# 2_x_Stepper_Motoren_Midi_Board_01.net
KiCad netlist of a schematic drawn in EAGLE
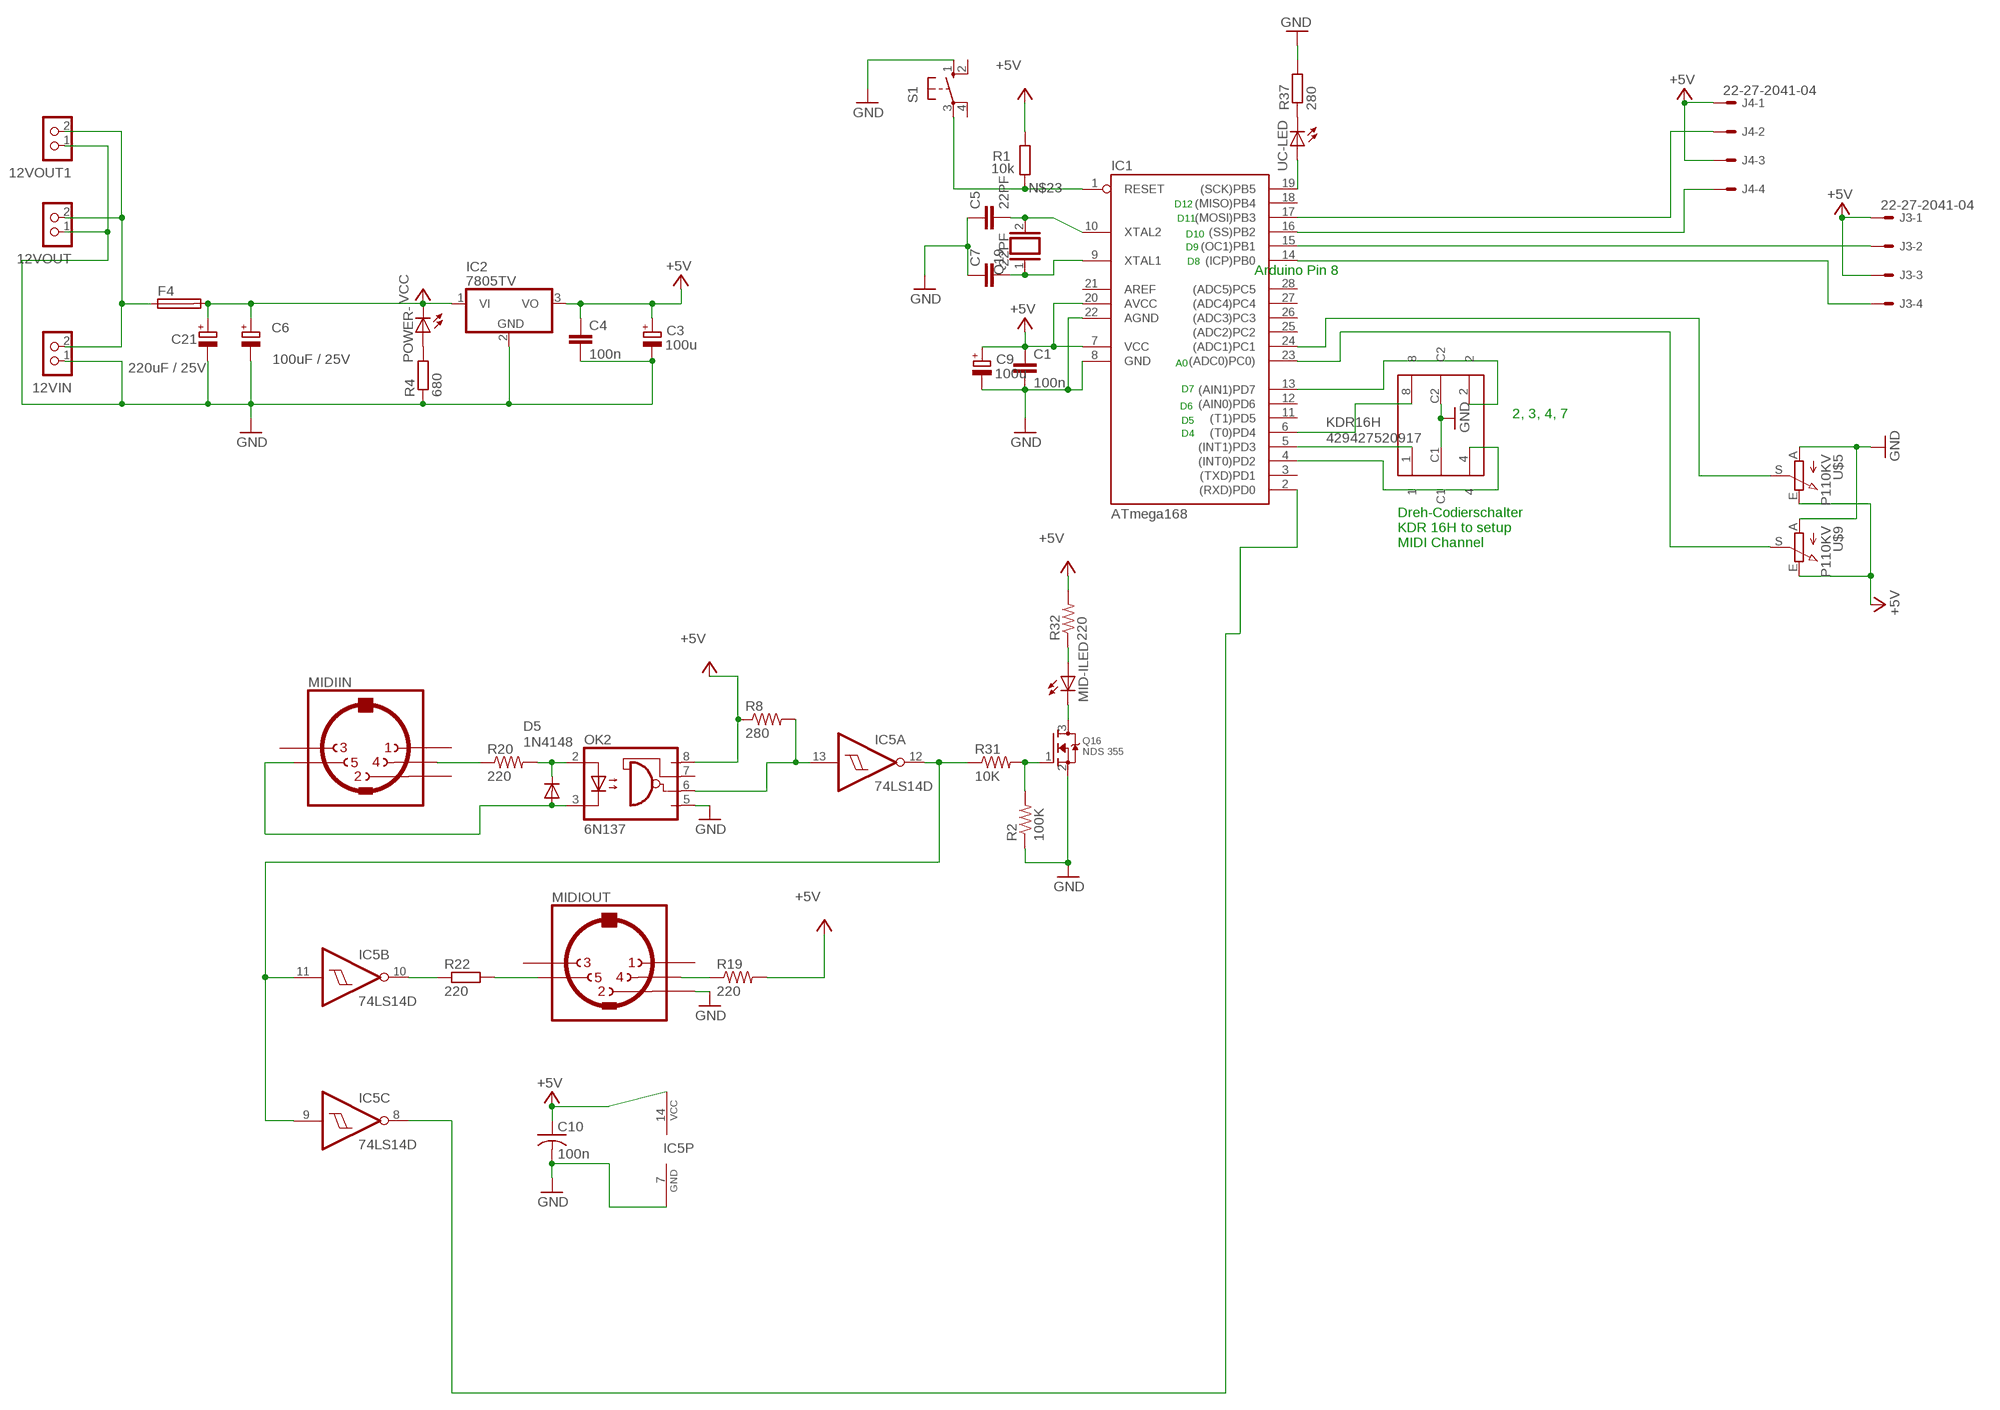
[diagram p0: schematic, sheet 1]

(export (version "E")
  (design (tool "Eeschema 10.0.6"))
  (components
    (comp (ref "12VIN")
      (value "CON_TERMINAL_BLOCK_02-5MM")
      (footprint "eagle-import:TERMINAL_BLOCK_2P_5")
      (libsource (lib "eagle-import") (part "CON_TERMINAL_BLOCK_02-5MM"))
    )
    (comp (ref "12VOUT")
      (value "CON_TERMINAL_BLOCK_02-5MM")
      (footprint "eagle-import:TERMINAL_BLOCK_2P_5")
      (libsource (lib "eagle-import") (part "CON_TERMINAL_BLOCK_02-5MM"))
    )
    (comp (ref "12VOUT1")
      (value "CON_TERMINAL_BLOCK_02-5MM")
      (footprint "eagle-import:TERMINAL_BLOCK_2P_5")
      (libsource (lib "eagle-import") (part "CON_TERMINAL_BLOCK_02-5MM"))
    )
    (comp (ref "C1")
      (value "100n")
      (footprint "eagle-import:C0805K")
      (libsource (lib "eagle-import") (part "C-EUC0805K"))
    )
    (comp (ref "C3")
      (value "100u")
      (footprint "eagle-import:E2,5-7")
      (libsource (lib "eagle-import") (part "CPOL-EUE2.5-7"))
    )
    (comp (ref "C4")
      (value "100n")
      (footprint "eagle-import:C0805K")
      (libsource (lib "eagle-import") (part "C-EUC0805K"))
    )
    (comp (ref "C5")
      (value "22PF")
      (footprint "eagle-import:C0805")
      (libsource (lib "eagle-import") (part "rcl_C-EUC0805"))
    )
    (comp (ref "C6")
      (value "100uF / 25V")
      (footprint "eagle-import:E2,5-7")
      (libsource (lib "eagle-import") (part "CPOL-EUE2.5-7"))
    )
    (comp (ref "C7")
      (value "22PF")
      (footprint "eagle-import:C0805")
      (libsource (lib "eagle-import") (part "rcl_C-EUC0805"))
    )
    (comp (ref "C9")
      (value "100u")
      (footprint "eagle-import:E2,5-6")
      (libsource (lib "eagle-import") (part "CPOL-EUE2.5-6"))
    )
    (comp (ref "C10")
      (value "100n")
      (footprint "eagle-import:C0805")
      (libsource (lib "eagle-import") (part "C-USC0805"))
    )
    (comp (ref "C21")
      (value "220uF / 25V")
      (footprint "eagle-import:E5-8,5")
      (libsource (lib "eagle-import") (part "rcl_CPOL-EUE5-8.5"))
    )
    (comp (ref "D5")
      (value "1N4148")
      (footprint "eagle-import:D-7.5")
      (libsource (lib "eagle-import") (part "DIODE-D-7.5"))
    )
    (comp (ref "F4")
      (value "SH22,5")
      (footprint "eagle-import:SH22,5")
      (fields (field (name "MF") "SCHURTER") (field (name "MPN") "0031.8201"))
      (libsource (lib "eagle-import") (part "SH22,5"))
    )
    (comp (ref "IC1")
      (value "ATmega168")
      (footprint "eagle-import:DIL28-3")
      (libsource (lib "eagle-import") (part "AT90S4433P"))
    )
    (comp (ref "IC2")
      (value "7805TV")
      (footprint "eagle-import:TO220V")
      (libsource (lib "eagle-import") (part "78TV05"))
    )
    (comp (ref "IC5")
      (value "74LS14D")
      (footprint "eagle-import:SO14")
      (libsource (lib "eagle-import") (part "7414DLS"))
    )
    (comp (ref "J3")
      (value "22-27-2041-04")
      (footprint "eagle-import:6410-04")
      (libsource (lib "eagle-import") (part "22-?-0427-2041"))
    )
    (comp (ref "J4")
      (value "22-27-2041-04")
      (footprint "eagle-import:6410-04")
      (libsource (lib "eagle-import") (part "22-?-0427-2041"))
    )
    (comp (ref "KDR16H")
      (value "429427520917")
      (footprint "eagle-import:429427520917")
      (libsource (lib "eagle-import") (part "429427520917"))
    )
    (comp (ref "MID-ILED")
      (value "LED3MM")
      (footprint "eagle-import:LED3MM")
      (libsource (lib "eagle-import") (part "LED3MM"))
    )
    (comp (ref "MIDIIN")
      (value "MAB5SH")
      (footprint "eagle-import:MAB5SH")
      (libsource (lib "eagle-import") (part "MAB5SH"))
    )
    (comp (ref "MIDIOUT")
      (value "MAB5SH")
      (footprint "eagle-import:MAB5SH")
      (libsource (lib "eagle-import") (part "MAB5SH"))
    )
    (comp (ref "OK2")
      (value "6N137")
      (footprint "eagle-import:DIL08")
      (fields
        (field (name "MPN") "6N137")
        (field (name "OC_FARNELL") "1328376")
        (field (name "OC_NEWARK") "52M1895")
      )
      (libsource (lib "eagle-import") (part "6N137"))
    )
    (comp (ref "POWER-")
      (value "LED3MM")
      (footprint "eagle-import:LED3MM")
      (libsource (lib "eagle-import") (part "LED3MM"))
    )
    (comp (ref "Q16")
      (value "NDS 355")
      (footprint "eagle-import:SOT23-W")
      (libsource (lib "eagle-import") (part "MOSFET-NWAVE"))
    )
    (comp (ref "Q19")
      (value "XTAL/S")
      (footprint "eagle-import:QS")
      (libsource (lib "eagle-import") (part "XTAL/S"))
    )
    (comp (ref "R1")
      (value "10k")
      (footprint "eagle-import:R0805")
      (libsource (lib "eagle-import") (part "R-EU_R0805"))
    )
    (comp (ref "R2")
      (value "100K")
      (footprint "eagle-import:R0805W")
      (libsource (lib "eagle-import") (part "R-US_R0805W"))
    )
    (comp (ref "R4")
      (value "680")
      (footprint "eagle-import:R0805W")
      (libsource (lib "eagle-import") (part "R-EU_R0805W"))
    )
    (comp (ref "R8")
      (value "280")
      (footprint "eagle-import:M0805")
      (libsource (lib "eagle-import") (part "R-US_M0805"))
    )
    (comp (ref "R19")
      (value "220")
      (footprint "eagle-import:R0805W")
      (libsource (lib "eagle-import") (part "R-US_R0805W"))
    )
    (comp (ref "R20")
      (value "220")
      (footprint "eagle-import:R0805")
      (libsource (lib "eagle-import") (part "R-US_R0805"))
    )
    (comp (ref "R22")
      (value "220")
      (footprint "eagle-import:R0805")
      (libsource (lib "eagle-import") (part "R-EU_R0805"))
    )
    (comp (ref "R31")
      (value "10K")
      (footprint "eagle-import:R0805W")
      (libsource (lib "eagle-import") (part "R-US_R0805W"))
    )
    (comp (ref "R32")
      (value "220")
      (footprint "eagle-import:R0805W")
      (libsource (lib "eagle-import") (part "R-US_R0805W"))
    )
    (comp (ref "R37")
      (value "280")
      (footprint "eagle-import:R0805")
      (libsource (lib "eagle-import") (part "R-EU_R0805"))
    )
    (comp (ref "S1")
      (value "10-XX")
      (footprint "eagle-import:B3F-10XX")
      (fields (field (name "MPN") "B3F-1000"))
      (libsource (lib "eagle-import") (part "10-XX"))
    )
    (comp (ref "U$5")
      (value "P110KV")
      (footprint "eagle-import:POT-P110KV")
      (libsource (lib "eagle-import") (part "P110KV"))
    )
    (comp (ref "U$9")
      (value "P110KV")
      (footprint "eagle-import:POT-P110KV")
      (libsource (lib "eagle-import") (part "P110KV"))
    )
    (comp (ref "UC-LED")
      (value "LED3MM")
      (footprint "eagle-import:LED3MM")
      (libsource (lib "eagle-import") (part "LED3MM"))
    )
  )
  (nets
    (net (code "1") (name "+5V") (class "Default")
      (node (ref "C1") (pin "1") (pinfunction "1_1") (pintype "passive"))
      (node (ref "C10") (pin "1") (pinfunction "1_1") (pintype "passive"))
      (node (ref "C3") (pin "+") (pinfunction "+_+") (pintype "passive"))
      (node (ref "C4") (pin "1") (pinfunction "1_1") (pintype "passive"))
      (node (ref "C9") (pin "+") (pinfunction "+_+") (pintype "passive"))
      (node (ref "IC1") (pin "20") (pinfunction "AVCC_20") (pintype "power_in"))
      (node (ref "IC1") (pin "7") (pinfunction "VCC_7") (pintype "power_in"))
      (node (ref "IC2") (pin "3") (pinfunction "VO_3") (pintype "passive"))
      (node (ref "IC5") (pin "14") (pinfunction "VCC_14") (pintype "power_in"))
      (node (ref "J3") (pin "1") (pinfunction "S_1") (pintype "passive"))
      (node (ref "J3") (pin "3") (pinfunction "S_3") (pintype "passive"))
      (node (ref "J4") (pin "1") (pinfunction "S_1") (pintype "passive"))
      (node (ref "J4") (pin "3") (pinfunction "S_3") (pintype "passive"))
      (node (ref "OK2") (pin "8") (pinfunction "VCC_8") (pintype "passive"))
      (node (ref "R1") (pin "2") (pinfunction "2_2") (pintype "passive"))
      (node (ref "R19") (pin "2") (pinfunction "2_2") (pintype "passive"))
      (node (ref "R32") (pin "2") (pinfunction "2_2") (pintype "passive"))
      (node (ref "R8") (pin "1") (pinfunction "1_1") (pintype "passive"))
      (node (ref "U$5") (pin "E") (pinfunction "E_E") (pintype "passive"))
      (node (ref "U$9") (pin "E") (pinfunction "E_E") (pintype "passive"))
    )
    (net (code "2") (name "/N$23") (class "Default")
      (node (ref "IC1") (pin "1") (pinfunction "RESET_1") (pintype "input"))
      (node (ref "R1") (pin "1") (pinfunction "1_1") (pintype "passive"))
      (node (ref "S1") (pin "3") (pinfunction "P_3") (pintype "passive"))
    )
    (net (code "3") (name "GND") (class "Default")
      (node (ref "12VIN") (pin "1") (pinfunction "1_1") (pintype "passive"))
      (node (ref "12VOUT") (pin "1") (pinfunction "1_1") (pintype "passive"))
      (node (ref "12VOUT1") (pin "1") (pinfunction "1_1") (pintype "passive"))
      (node (ref "C1") (pin "2") (pinfunction "2_2") (pintype "passive"))
      (node (ref "C10") (pin "2") (pinfunction "2_2") (pintype "passive"))
      (node (ref "C21") (pin "-") (pinfunction "-_-") (pintype "passive"))
      (node (ref "C3") (pin "-") (pinfunction "-_-") (pintype "passive"))
      (node (ref "C4") (pin "2") (pinfunction "2_2") (pintype "passive"))
      (node (ref "C5") (pin "1") (pinfunction "1_1") (pintype "passive"))
      (node (ref "C6") (pin "-") (pinfunction "-_-") (pintype "passive"))
      (node (ref "C7") (pin "1") (pinfunction "1_1") (pintype "passive"))
      (node (ref "C9") (pin "-") (pinfunction "-_-") (pintype "passive"))
      (node (ref "IC1") (pin "22") (pinfunction "AGND_22") (pintype "power_in"))
      (node (ref "IC1") (pin "8") (pinfunction "GND_8") (pintype "power_in"))
      (node (ref "IC2") (pin "2") (pinfunction "GND_2") (pintype "passive"))
      (node (ref "IC5") (pin "7") (pinfunction "GND_7") (pintype "power_in"))
      (node (ref "KDR16H") (pin "C1") (pinfunction "C1_C1") (pintype "bidirectional"))
      (node (ref "KDR16H") (pin "C2") (pinfunction "C2_C2") (pintype "bidirectional"))
      (node (ref "MIDIOUT") (pin "2") (pinfunction "2_2") (pintype "passive"))
      (node (ref "OK2") (pin "5") (pinfunction "GND_5") (pintype "passive"))
      (node (ref "Q16") (pin "2") (pinfunction "S_2") (pintype "bidirectional"))
      (node (ref "R2") (pin "1") (pinfunction "1_1") (pintype "passive"))
      (node (ref "R37") (pin "2") (pinfunction "2_2") (pintype "passive"))
      (node (ref "R4") (pin "1") (pinfunction "1_1") (pintype "passive"))
      (node (ref "S1") (pin "1") (pinfunction "S_1") (pintype "passive"))
      (node (ref "U$5") (pin "A") (pinfunction "A_A") (pintype "passive"))
      (node (ref "U$9") (pin "A") (pinfunction "A_A") (pintype "passive"))
    )
    (net (code "4") (name "Net-(12VIN-Pad2)") (class "Default")
      (node (ref "12VIN") (pin "2") (pinfunction "2_2") (pintype "passive"))
      (node (ref "12VOUT") (pin "2") (pinfunction "2_2") (pintype "passive"))
      (node (ref "12VOUT1") (pin "2") (pinfunction "2_2") (pintype "passive"))
      (node (ref "F4") (pin "1") (pinfunction "1_1") (pintype "passive"))
    )
    (net (code "5") (name "Net-(IC1-(ADC0)PC0))") (class "Default")
      (node (ref "IC1") (pin "23") (pinfunction "(ADC0)PC0)_23") (pintype "bidirectional"))
      (node (ref "U$9") (pin "S") (pinfunction "S_S") (pintype "passive"))
    )
    (net (code "6") (name "Net-(IC1-(ADC1)PC1)") (class "Default")
      (node (ref "IC1") (pin "24") (pinfunction "(ADC1)PC1_24") (pintype "bidirectional"))
      (node (ref "U$5") (pin "S") (pinfunction "S_S") (pintype "passive"))
    )
    (net (code "7") (name "Net-(IC1-(AIN1)PD7)") (class "Default")
      (node (ref "IC1") (pin "13") (pinfunction "(AIN1)PD7_13") (pintype "bidirectional"))
      (node (ref "KDR16H") (pin "2") (pinfunction "2_2") (pintype "bidirectional"))
    )
    (net (code "8") (name "Net-(IC1-(ICP)PB0)") (class "Default")
      (node (ref "IC1") (pin "14") (pinfunction "(ICP)PB0_14") (pintype "bidirectional"))
      (node (ref "J3") (pin "4") (pinfunction "S_4") (pintype "passive"))
    )
    (net (code "9") (name "Net-(IC1-(INT0)PD2)") (class "Default")
      (node (ref "IC1") (pin "4") (pinfunction "(INT0)PD2_4") (pintype "bidirectional"))
      (node (ref "KDR16H") (pin "4") (pinfunction "4_4") (pintype "bidirectional"))
    )
    (net (code "10") (name "Net-(IC1-(INT1)PD3)") (class "Default")
      (node (ref "IC1") (pin "5") (pinfunction "(INT1)PD3_5") (pintype "bidirectional"))
      (node (ref "KDR16H") (pin "1") (pinfunction "1_1") (pintype "bidirectional"))
    )
    (net (code "11") (name "Net-(IC1-(MOSI)PB3)") (class "Default")
      (node (ref "IC1") (pin "17") (pinfunction "(MOSI)PB3_17") (pintype "bidirectional"))
      (node (ref "J4") (pin "2") (pinfunction "S_2") (pintype "passive"))
    )
    (net (code "12") (name "Net-(IC1-(OC1)PB1)") (class "Default")
      (node (ref "IC1") (pin "15") (pinfunction "(OC1)PB1_15") (pintype "bidirectional"))
      (node (ref "J3") (pin "2") (pinfunction "S_2") (pintype "passive"))
    )
    (net (code "13") (name "Net-(IC1-(RXD)PD0)") (class "Default")
      (node (ref "IC1") (pin "2") (pinfunction "(RXD)PD0_2") (pintype "bidirectional"))
      (node (ref "IC5") (pin "8") (pinfunction "O_8") (pintype "output"))
    )
    (net (code "14") (name "Net-(IC1-(SCK)PB5)") (class "Default")
      (node (ref "IC1") (pin "19") (pinfunction "(SCK)PB5_19") (pintype "bidirectional"))
      (node (ref "UC-LED") (pin "A") (pinfunction "A_A") (pintype "passive"))
    )
    (net (code "15") (name "Net-(IC1-(SS)PB2)") (class "Default")
      (node (ref "IC1") (pin "16") (pinfunction "(SS)PB2_16") (pintype "bidirectional"))
      (node (ref "J4") (pin "4") (pinfunction "S_4") (pintype "passive"))
    )
    (net (code "16") (name "Net-(IC1-(T0)PD4)") (class "Default")
      (node (ref "IC1") (pin "6") (pinfunction "(T0)PD4_6") (pintype "bidirectional"))
      (node (ref "KDR16H") (pin "8") (pinfunction "8_8") (pintype "bidirectional"))
    )
    (net (code "17") (name "Net-(IC1-XTAL1)") (class "Default")
      (node (ref "C7") (pin "2") (pinfunction "2_2") (pintype "passive"))
      (node (ref "IC1") (pin "9") (pinfunction "XTAL1_9") (pintype "bidirectional"))
      (node (ref "Q19") (pin "1") (pinfunction "1_1") (pintype "passive"))
    )
    (net (code "18") (name "Net-(IC1-XTAL2)") (class "Default")
      (node (ref "C5") (pin "2") (pinfunction "2_2") (pintype "passive"))
      (node (ref "IC1") (pin "10") (pinfunction "XTAL2_10") (pintype "bidirectional"))
      (node (ref "Q19") (pin "2") (pinfunction "2_2") (pintype "passive"))
    )
    (net (code "19") (name "Net-(IC5A-I)") (class "Default")
      (node (ref "IC5") (pin "13") (pinfunction "I_13") (pintype "input"))
      (node (ref "OK2") (pin "6") (pinfunction "VO_6") (pintype "passive"))
      (node (ref "R8") (pin "2") (pinfunction "2_2") (pintype "passive"))
    )
    (net (code "20") (name "Net-(IC5A-O)") (class "Default")
      (node (ref "IC5") (pin "11") (pinfunction "I_11") (pintype "input"))
      (node (ref "IC5") (pin "12") (pinfunction "O_12") (pintype "output"))
      (node (ref "IC5") (pin "9") (pinfunction "I_9") (pintype "input"))
      (node (ref "R31") (pin "1") (pinfunction "1_1") (pintype "passive"))
    )
    (net (code "21") (name "Net-(IC5B-O)") (class "Default")
      (node (ref "IC5") (pin "10") (pinfunction "O_10") (pintype "output"))
      (node (ref "R22") (pin "1") (pinfunction "1_1") (pintype "passive"))
    )
    (net (code "22") (name "Net-(MID-ILED-C)") (class "Default")
      (node (ref "MID-ILED") (pin "K") (pinfunction "C_K") (pintype "passive"))
      (node (ref "Q16") (pin "3") (pinfunction "D_3") (pintype "bidirectional"))
    )
    (net (code "23") (name "Net-(MID-ILED-PadA)") (class "Default")
      (node (ref "MID-ILED") (pin "A") (pinfunction "A_A") (pintype "passive"))
      (node (ref "R32") (pin "1") (pinfunction "1_1") (pintype "passive"))
    )
    (net (code "24") (name "Net-(MIDIIN-Pad4)") (class "Default")
      (node (ref "MIDIIN") (pin "4") (pinfunction "4_4") (pintype "passive"))
      (node (ref "R20") (pin "1") (pinfunction "1_1") (pintype "passive"))
    )
    (net (code "25") (name "Net-(MIDIOUT-Pad4)") (class "Default")
      (node (ref "MIDIOUT") (pin "4") (pinfunction "4_4") (pintype "passive"))
      (node (ref "R19") (pin "1") (pinfunction "1_1") (pintype "passive"))
    )
    (net (code "26") (name "Net-(MIDIOUT-Pad5)") (class "Default")
      (node (ref "MIDIOUT") (pin "5") (pinfunction "5_5") (pintype "passive"))
      (node (ref "R22") (pin "2") (pinfunction "2_2") (pintype "passive"))
    )
    (net (code "27") (name "Net-(OK2-A)") (class "Default")
      (node (ref "D5") (pin "C") (pinfunction "C_C") (pintype "passive"))
      (node (ref "OK2") (pin "2") (pinfunction "A_2") (pintype "passive"))
      (node (ref "R20") (pin "2") (pinfunction "2_2") (pintype "passive"))
    )
    (net (code "28") (name "Net-(OK2-C)") (class "Default")
      (node (ref "D5") (pin "A") (pinfunction "A_A") (pintype "passive"))
      (node (ref "MIDIIN") (pin "5") (pinfunction "5_5") (pintype "passive"))
      (node (ref "OK2") (pin "3") (pinfunction "C_3") (pintype "passive"))
    )
    (net (code "29") (name "Net-(POWER--PadA)") (class "Default")
      (node (ref "POWER-") (pin "A") (pinfunction "A_A") (pintype "passive"))
      (node (ref "R4") (pin "2") (pinfunction "2_2") (pintype "passive"))
    )
    (net (code "30") (name "Net-(Q16-G)") (class "Default")
      (node (ref "Q16") (pin "1") (pinfunction "G_1") (pintype "bidirectional"))
      (node (ref "R2") (pin "2") (pinfunction "2_2") (pintype "passive"))
      (node (ref "R31") (pin "2") (pinfunction "2_2") (pintype "passive"))
    )
    (net (code "31") (name "Net-(UC-LED-C)") (class "Default")
      (node (ref "R37") (pin "1") (pinfunction "1_1") (pintype "passive"))
      (node (ref "UC-LED") (pin "K") (pinfunction "C_K") (pintype "passive"))
    )
    (net (code "32") (name "VCC") (class "Default")
      (node (ref "C21") (pin "+") (pinfunction "+_+") (pintype "passive"))
      (node (ref "C6") (pin "+") (pinfunction "+_+") (pintype "passive"))
      (node (ref "F4") (pin "2") (pinfunction "2_2") (pintype "passive"))
      (node (ref "IC2") (pin "1") (pinfunction "VI_1") (pintype "input"))
      (node (ref "POWER-") (pin "K") (pinfunction "C_K") (pintype "passive"))
    )
    (net (code "33") (name "unconnected-(IC1-(ADC2)PC2-Pad25)") (class "Default")
      (node (ref "IC1") (pin "25") (pinfunction "(ADC2)PC2_25") (pintype "bidirectional"))
    )
    (net (code "34") (name "unconnected-(IC1-(ADC3)PC3-Pad26)") (class "Default")
      (node (ref "IC1") (pin "26") (pinfunction "(ADC3)PC3_26") (pintype "bidirectional"))
    )
    (net (code "35") (name "unconnected-(IC1-(ADC4)PC4-Pad27)") (class "Default")
      (node (ref "IC1") (pin "27") (pinfunction "(ADC4)PC4_27") (pintype "bidirectional"))
    )
    (net (code "36") (name "unconnected-(IC1-(ADC5)PC5-Pad28)") (class "Default")
      (node (ref "IC1") (pin "28") (pinfunction "(ADC5)PC5_28") (pintype "bidirectional"))
    )
    (net (code "37") (name "unconnected-(IC1-(AIN0)PD6-Pad12)") (class "Default")
      (node (ref "IC1") (pin "12") (pinfunction "(AIN0)PD6_12") (pintype "bidirectional"))
    )
    (net (code "38") (name "unconnected-(IC1-(MISO)PB4-Pad18)") (class "Default")
      (node (ref "IC1") (pin "18") (pinfunction "(MISO)PB4_18") (pintype "bidirectional"))
    )
    (net (code "39") (name "unconnected-(IC1-(T1)PD5-Pad11)") (class "Default")
      (node (ref "IC1") (pin "11") (pinfunction "(T1)PD5_11") (pintype "bidirectional"))
    )
    (net (code "40") (name "unconnected-(IC1-(TXD)PD1-Pad3)") (class "Default")
      (node (ref "IC1") (pin "3") (pinfunction "(TXD)PD1_3") (pintype "bidirectional"))
    )
    (net (code "41") (name "unconnected-(IC1-AREF-Pad21)") (class "Default")
      (node (ref "IC1") (pin "21") (pinfunction "AREF_21") (pintype "passive"))
    )
    (net (code "42") (name "unconnected-(MIDIIN-Pad1)") (class "Default")
      (node (ref "MIDIIN") (pin "1") (pinfunction "1_1") (pintype "passive"))
    )
    (net (code "43") (name "unconnected-(MIDIIN-Pad2)") (class "Default")
      (node (ref "MIDIIN") (pin "2") (pinfunction "2_2") (pintype "passive"))
    )
    (net (code "44") (name "unconnected-(MIDIIN-Pad3)") (class "Default")
      (node (ref "MIDIIN") (pin "3") (pinfunction "3_3") (pintype "passive"))
    )
    (net (code "45") (name "unconnected-(MIDIOUT-Pad1)") (class "Default")
      (node (ref "MIDIOUT") (pin "1") (pinfunction "1_1") (pintype "passive"))
    )
    (net (code "46") (name "unconnected-(MIDIOUT-Pad3)") (class "Default")
      (node (ref "MIDIOUT") (pin "3") (pinfunction "3_3") (pintype "passive"))
    )
    (net (code "47") (name "unconnected-(OK2-VE-Pad7)") (class "Default")
      (node (ref "OK2") (pin "7") (pinfunction "VE_7") (pintype "passive"))
    )
    (net (code "48") (name "unconnected-(S1-P1-Pad4)") (class "Default")
      (node (ref "S1") (pin "4") (pinfunction "P1_4") (pintype "passive"))
    )
    (net (code "49") (name "unconnected-(S1-S1-Pad2)") (class "Default")
      (node (ref "S1") (pin "2") (pinfunction "S1_2") (pintype "passive"))
    )
  )
)
